# SOM_CD.net
KiCad netlist of a schematic drawn in Altium Designer
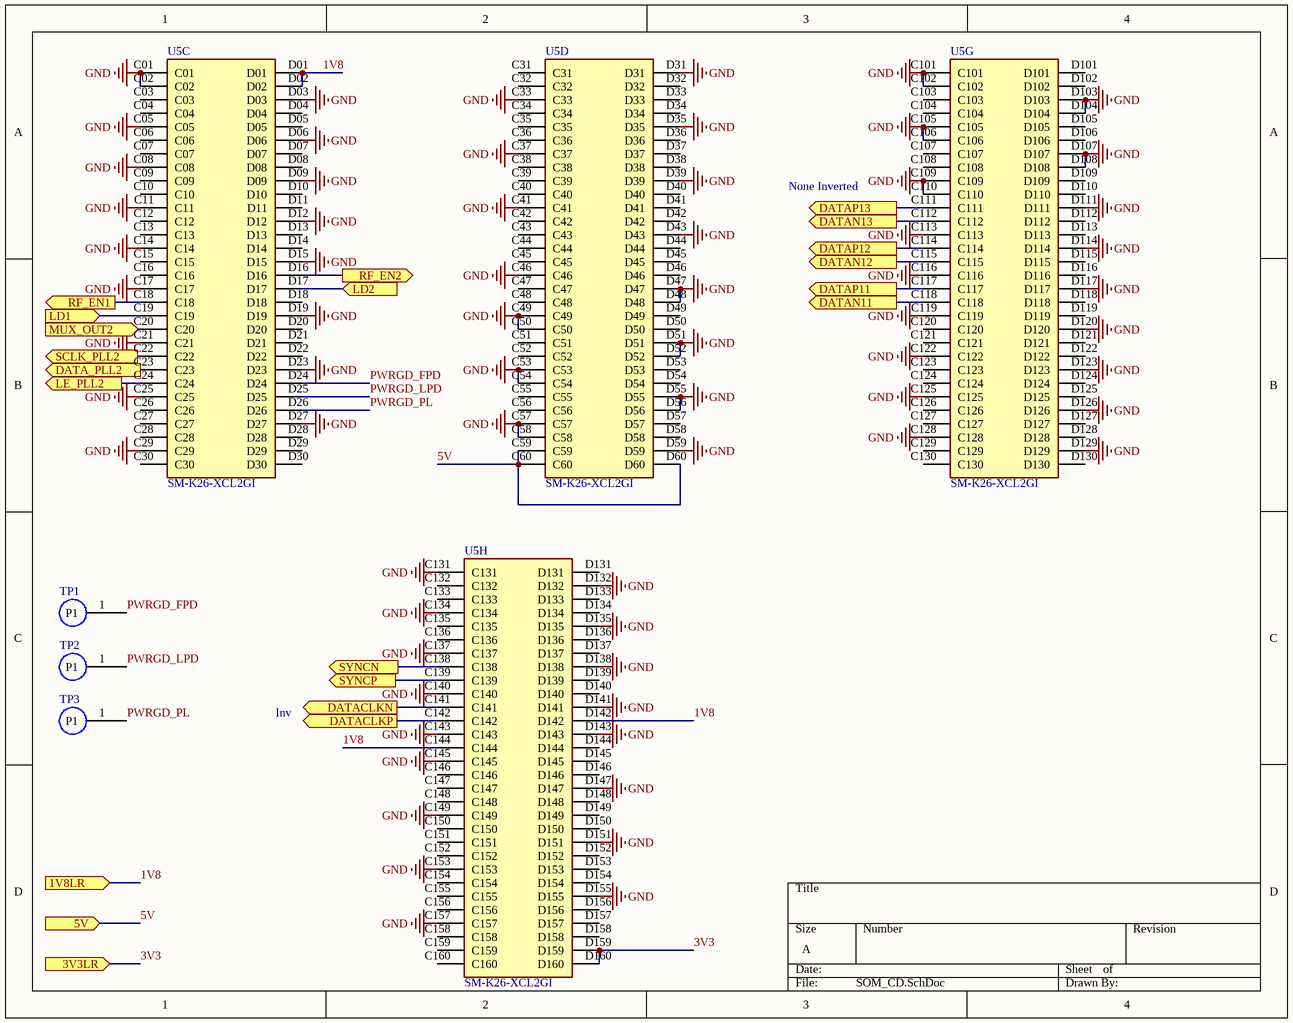
[diagram p0: SOM_CD.SchDoc]

(export (version "E")
  (design (tool "Eeschema 10.0.6"))
  (components
    (comp (ref "TP1") (value "~") (footprint "Testpoint") (libsource (lib "Schlib1") (part "Testpoint")))
    (comp (ref "TP2") (value "~") (footprint "Testpoint") (libsource (lib "Schlib1") (part "Testpoint")))
    (comp (ref "TP3") (value "~") (footprint "Testpoint") (libsource (lib "Schlib1") (part "Testpoint")))
    (comp (ref "U5")
      (value "SM-K26-XCL2GI")
      (footprint "MODULE_SM-K26-XCL2GI")
      (fields (field (name "MF") "Xilinx Inc."))
      (libsource (lib "Schlib1") (part "SM-K26-XCL2GI"))
    )
  )
  (nets
    (net (code "1") (name "/1V8") (class "Default")
      (node (ref "U5") (pin "C144") (pinfunction "C144_C144") (pintype "passive"))
      (node (ref "U5") (pin "D01") (pinfunction "D01_D01") (pintype "passive"))
      (node (ref "U5") (pin "D02") (pinfunction "D02_D02") (pintype "passive"))
      (node (ref "U5") (pin "D142") (pinfunction "D142_D142") (pintype "passive"))
    )
    (net (code "2") (name "/3V3") (class "Default")
      (node (ref "U5") (pin "D159") (pinfunction "D159_D159") (pintype "passive"))
      (node (ref "U5") (pin "D160") (pinfunction "D160_D160") (pintype "passive"))
    )
    (net (code "3") (name "/5V") (class "Default")
      (node (ref "U5") (pin "C59") (pinfunction "C59_C59") (pintype "passive"))
      (node (ref "U5") (pin "C60") (pinfunction "C60_C60") (pintype "passive"))
      (node (ref "U5") (pin "D60") (pinfunction "D60_D60") (pintype "passive"))
    )
    (net (code "4") (name "/DATACLKN") (class "Default")
      (node (ref "U5") (pin "C141") (pinfunction "C141_C141") (pintype "passive"))
    )
    (net (code "5") (name "/DATACLKP") (class "Default")
      (node (ref "U5") (pin "C142") (pinfunction "C142_C142") (pintype "passive"))
    )
    (net (code "6") (name "/DATAN11") (class "Default")
      (node (ref "U5") (pin "C118") (pinfunction "C118_C118") (pintype "passive"))
    )
    (net (code "7") (name "/DATAN12") (class "Default")
      (node (ref "U5") (pin "C115") (pinfunction "C115_C115") (pintype "passive"))
    )
    (net (code "8") (name "/DATAN13") (class "Default")
      (node (ref "U5") (pin "C112") (pinfunction "C112_C112") (pintype "passive"))
    )
    (net (code "9") (name "/DATAP11") (class "Default")
      (node (ref "U5") (pin "C117") (pinfunction "C117_C117") (pintype "passive"))
    )
    (net (code "10") (name "/DATAP12") (class "Default")
      (node (ref "U5") (pin "C114") (pinfunction "C114_C114") (pintype "passive"))
    )
    (net (code "11") (name "/DATAP13") (class "Default")
      (node (ref "U5") (pin "C111") (pinfunction "C111_C111") (pintype "passive"))
    )
    (net (code "12") (name "/DATA_PLL2") (class "Default")
      (node (ref "U5") (pin "C23") (pinfunction "C23_C23") (pintype "passive"))
    )
    (net (code "13") (name "/LD1") (class "Default")
      (node (ref "U5") (pin "C19") (pinfunction "C19_C19") (pintype "passive"))
    )
    (net (code "14") (name "/LD2") (class "Default")
      (node (ref "U5") (pin "D17") (pinfunction "D17_D17") (pintype "passive"))
    )
    (net (code "15") (name "/LE_PLL2") (class "Default")
      (node (ref "U5") (pin "C24") (pinfunction "C24_C24") (pintype "passive"))
    )
    (net (code "16") (name "/MUX_OUT2") (class "Default")
      (node (ref "U5") (pin "C20") (pinfunction "C20_C20") (pintype "passive"))
    )
    (net (code "17") (name "/PWRGD_FPD") (class "Default")
      (node (ref "TP1") (pin "1") (pinfunction "P1_1") (pintype "passive"))
      (node (ref "U5") (pin "D24") (pinfunction "D24_D24") (pintype "passive"))
    )
    (net (code "18") (name "/PWRGD_LPD") (class "Default")
      (node (ref "TP2") (pin "1") (pinfunction "P1_1") (pintype "passive"))
      (node (ref "U5") (pin "D25") (pinfunction "D25_D25") (pintype "passive"))
    )
    (net (code "19") (name "/PWRGD_PL") (class "Default")
      (node (ref "TP3") (pin "1") (pinfunction "P1_1") (pintype "passive"))
      (node (ref "U5") (pin "D26") (pinfunction "D26_D26") (pintype "passive"))
    )
    (net (code "20") (name "/RF_EN1") (class "Default")
      (node (ref "U5") (pin "C18") (pinfunction "C18_C18") (pintype "passive"))
    )
    (net (code "21") (name "/RF_EN2") (class "Default")
      (node (ref "U5") (pin "D16") (pinfunction "D16_D16") (pintype "passive"))
    )
    (net (code "22") (name "/SCLK_PLL2") (class "Default")
      (node (ref "U5") (pin "C22") (pinfunction "C22_C22") (pintype "passive"))
    )
    (net (code "23") (name "/SYNCN") (class "Default")
      (node (ref "U5") (pin "C138") (pinfunction "C138_C138") (pintype "passive"))
    )
    (net (code "24") (name "/SYNCP") (class "Default")
      (node (ref "U5") (pin "C139") (pinfunction "C139_C139") (pintype "passive"))
    )
    (net (code "25") (name "GND") (class "Default")
      (node (ref "U5") (pin "C01") (pinfunction "C01_C01") (pintype "passive"))
      (node (ref "U5") (pin "C02") (pinfunction "C02_C02") (pintype "passive"))
      (node (ref "U5") (pin "C05") (pinfunction "C05_C05") (pintype "passive"))
      (node (ref "U5") (pin "C08") (pinfunction "C08_C08") (pintype "passive"))
      (node (ref "U5") (pin "C101") (pinfunction "C101_C101") (pintype "passive"))
      (node (ref "U5") (pin "C102") (pinfunction "C102_C102") (pintype "passive"))
      (node (ref "U5") (pin "C105") (pinfunction "C105_C105") (pintype "passive"))
      (node (ref "U5") (pin "C106") (pinfunction "C106_C106") (pintype "passive"))
      (node (ref "U5") (pin "C109") (pinfunction "C109_C109") (pintype "passive"))
      (node (ref "U5") (pin "C11") (pinfunction "C11_C11") (pintype "passive"))
      (node (ref "U5") (pin "C110") (pinfunction "C110_C110") (pintype "passive"))
      (node (ref "U5") (pin "C113") (pinfunction "C113_C113") (pintype "passive"))
      (node (ref "U5") (pin "C116") (pinfunction "C116_C116") (pintype "passive"))
      (node (ref "U5") (pin "C119") (pinfunction "C119_C119") (pintype "passive"))
      (node (ref "U5") (pin "C122") (pinfunction "C122_C122") (pintype "passive"))
      (node (ref "U5") (pin "C125") (pinfunction "C125_C125") (pintype "passive"))
      (node (ref "U5") (pin "C128") (pinfunction "C128_C128") (pintype "passive"))
      (node (ref "U5") (pin "C131") (pinfunction "C131_C131") (pintype "passive"))
      (node (ref "U5") (pin "C134") (pinfunction "C134_C134") (pintype "passive"))
      (node (ref "U5") (pin "C137") (pinfunction "C137_C137") (pintype "passive"))
      (node (ref "U5") (pin "C14") (pinfunction "C14_C14") (pintype "passive"))
      (node (ref "U5") (pin "C140") (pinfunction "C140_C140") (pintype "passive"))
      (node (ref "U5") (pin "C143") (pinfunction "C143_C143") (pintype "passive"))
      (node (ref "U5") (pin "C145") (pinfunction "C145_C145") (pintype "passive"))
      (node (ref "U5") (pin "C149") (pinfunction "C149_C149") (pintype "passive"))
      (node (ref "U5") (pin "C153") (pinfunction "C153_C153") (pintype "passive"))
      (node (ref "U5") (pin "C157") (pinfunction "C157_C157") (pintype "passive"))
      (node (ref "U5") (pin "C17") (pinfunction "C17_C17") (pintype "passive"))
      (node (ref "U5") (pin "C21") (pinfunction "C21_C21") (pintype "passive"))
      (node (ref "U5") (pin "C25") (pinfunction "C25_C25") (pintype "passive"))
      (node (ref "U5") (pin "C29") (pinfunction "C29_C29") (pintype "passive"))
      (node (ref "U5") (pin "C33") (pinfunction "C33_C33") (pintype "passive"))
      (node (ref "U5") (pin "C37") (pinfunction "C37_C37") (pintype "passive"))
      (node (ref "U5") (pin "C41") (pinfunction "C41_C41") (pintype "passive"))
      (node (ref "U5") (pin "C46") (pinfunction "C46_C46") (pintype "passive"))
      (node (ref "U5") (pin "C49") (pinfunction "C49_C49") (pintype "passive"))
      (node (ref "U5") (pin "C50") (pinfunction "C50_C50") (pintype "passive"))
      (node (ref "U5") (pin "C53") (pinfunction "C53_C53") (pintype "passive"))
      (node (ref "U5") (pin "C54") (pinfunction "C54_C54") (pintype "passive"))
      (node (ref "U5") (pin "C57") (pinfunction "C57_C57") (pintype "passive"))
      (node (ref "U5") (pin "C58") (pinfunction "C58_C58") (pintype "passive"))
      (node (ref "U5") (pin "D03") (pinfunction "D03_D03") (pintype "passive"))
      (node (ref "U5") (pin "D06") (pinfunction "D06_D06") (pintype "passive"))
      (node (ref "U5") (pin "D09") (pinfunction "D09_D09") (pintype "passive"))
      (node (ref "U5") (pin "D103") (pinfunction "D103_D103") (pintype "passive"))
      (node (ref "U5") (pin "D104") (pinfunction "D104_D104") (pintype "passive"))
      (node (ref "U5") (pin "D107") (pinfunction "D107_D107") (pintype "passive"))
      (node (ref "U5") (pin "D108") (pinfunction "D108_D108") (pintype "passive"))
      (node (ref "U5") (pin "D111") (pinfunction "D111_D111") (pintype "passive"))
      (node (ref "U5") (pin "D114") (pinfunction "D114_D114") (pintype "passive"))
      (node (ref "U5") (pin "D117") (pinfunction "D117_D117") (pintype "passive"))
      (node (ref "U5") (pin "D12") (pinfunction "D12_D12") (pintype "passive"))
      (node (ref "U5") (pin "D120") (pinfunction "D120_D120") (pintype "passive"))
      (node (ref "U5") (pin "D123") (pinfunction "D123_D123") (pintype "passive"))
      (node (ref "U5") (pin "D126") (pinfunction "D126_D126") (pintype "passive"))
      (node (ref "U5") (pin "D129") (pinfunction "D129_D129") (pintype "passive"))
      (node (ref "U5") (pin "D132") (pinfunction "D132_D132") (pintype "passive"))
      (node (ref "U5") (pin "D135") (pinfunction "D135_D135") (pintype "passive"))
      (node (ref "U5") (pin "D138") (pinfunction "D138_D138") (pintype "passive"))
      (node (ref "U5") (pin "D141") (pinfunction "D141_D141") (pintype "passive"))
      (node (ref "U5") (pin "D143") (pinfunction "D143_D143") (pintype "passive"))
      (node (ref "U5") (pin "D147") (pinfunction "D147_D147") (pintype "passive"))
      (node (ref "U5") (pin "D15") (pinfunction "D15_D15") (pintype "passive"))
      (node (ref "U5") (pin "D151") (pinfunction "D151_D151") (pintype "passive"))
      (node (ref "U5") (pin "D155") (pinfunction "D155_D155") (pintype "passive"))
      (node (ref "U5") (pin "D19") (pinfunction "D19_D19") (pintype "passive"))
      (node (ref "U5") (pin "D23") (pinfunction "D23_D23") (pintype "passive"))
      (node (ref "U5") (pin "D27") (pinfunction "D27_D27") (pintype "passive"))
      (node (ref "U5") (pin "D31") (pinfunction "D31_D31") (pintype "passive"))
      (node (ref "U5") (pin "D35") (pinfunction "D35_D35") (pintype "passive"))
      (node (ref "U5") (pin "D39") (pinfunction "D39_D39") (pintype "passive"))
      (node (ref "U5") (pin "D43") (pinfunction "D43_D43") (pintype "passive"))
      (node (ref "U5") (pin "D47") (pinfunction "D47_D47") (pintype "passive"))
      (node (ref "U5") (pin "D48") (pinfunction "D48_D48") (pintype "passive"))
      (node (ref "U5") (pin "D51") (pinfunction "D51_D51") (pintype "passive"))
      (node (ref "U5") (pin "D52") (pinfunction "D52_D52") (pintype "passive"))
      (node (ref "U5") (pin "D55") (pinfunction "D55_D55") (pintype "passive"))
      (node (ref "U5") (pin "D56") (pinfunction "D56_D56") (pintype "passive"))
      (node (ref "U5") (pin "D59") (pinfunction "D59_D59") (pintype "passive"))
    )
    (net (code "26") (name "unconnected-(U5-PadC03)") (class "Default")
      (node (ref "U5") (pin "C03") (pinfunction "C03_C03") (pintype "passive"))
    )
    (net (code "27") (name "unconnected-(U5-PadC04)") (class "Default")
      (node (ref "U5") (pin "C04") (pinfunction "C04_C04") (pintype "passive"))
    )
    (net (code "28") (name "unconnected-(U5-PadC06)") (class "Default")
      (node (ref "U5") (pin "C06") (pinfunction "C06_C06") (pintype "passive"))
    )
    (net (code "29") (name "unconnected-(U5-PadC07)") (class "Default")
      (node (ref "U5") (pin "C07") (pinfunction "C07_C07") (pintype "passive"))
    )
    (net (code "30") (name "unconnected-(U5-PadC09)") (class "Default")
      (node (ref "U5") (pin "C09") (pinfunction "C09_C09") (pintype "passive"))
    )
    (net (code "31") (name "unconnected-(U5-PadC10)") (class "Default")
      (node (ref "U5") (pin "C10") (pinfunction "C10_C10") (pintype "passive"))
    )
    (net (code "32") (name "unconnected-(U5-PadC12)") (class "Default")
      (node (ref "U5") (pin "C12") (pinfunction "C12_C12") (pintype "passive"))
    )
    (net (code "33") (name "unconnected-(U5-PadC13)") (class "Default")
      (node (ref "U5") (pin "C13") (pinfunction "C13_C13") (pintype "passive"))
    )
    (net (code "34") (name "unconnected-(U5-PadC15)") (class "Default")
      (node (ref "U5") (pin "C15") (pinfunction "C15_C15") (pintype "passive"))
    )
    (net (code "35") (name "unconnected-(U5-PadC16)") (class "Default")
      (node (ref "U5") (pin "C16") (pinfunction "C16_C16") (pintype "passive"))
    )
    (net (code "36") (name "unconnected-(U5-PadC26)") (class "Default")
      (node (ref "U5") (pin "C26") (pinfunction "C26_C26") (pintype "passive"))
    )
    (net (code "37") (name "unconnected-(U5-PadC27)") (class "Default")
      (node (ref "U5") (pin "C27") (pinfunction "C27_C27") (pintype "passive"))
    )
    (net (code "38") (name "unconnected-(U5-PadC28)") (class "Default")
      (node (ref "U5") (pin "C28") (pinfunction "C28_C28") (pintype "passive"))
    )
    (net (code "39") (name "unconnected-(U5-PadC30)") (class "Default")
      (node (ref "U5") (pin "C30") (pinfunction "C30_C30") (pintype "passive"))
    )
    (net (code "40") (name "unconnected-(U5-PadC31)") (class "Default")
      (node (ref "U5") (pin "C31") (pinfunction "C31_C31") (pintype "passive"))
    )
    (net (code "41") (name "unconnected-(U5-PadC32)") (class "Default")
      (node (ref "U5") (pin "C32") (pinfunction "C32_C32") (pintype "passive"))
    )
    (net (code "42") (name "unconnected-(U5-PadC34)") (class "Default")
      (node (ref "U5") (pin "C34") (pinfunction "C34_C34") (pintype "passive"))
    )
    (net (code "43") (name "unconnected-(U5-PadC35)") (class "Default")
      (node (ref "U5") (pin "C35") (pinfunction "C35_C35") (pintype "passive"))
    )
    (net (code "44") (name "unconnected-(U5-PadC36)") (class "Default")
      (node (ref "U5") (pin "C36") (pinfunction "C36_C36") (pintype "passive"))
    )
    (net (code "45") (name "unconnected-(U5-PadC38)") (class "Default")
      (node (ref "U5") (pin "C38") (pinfunction "C38_C38") (pintype "passive"))
    )
    (net (code "46") (name "unconnected-(U5-PadC39)") (class "Default")
      (node (ref "U5") (pin "C39") (pinfunction "C39_C39") (pintype "passive"))
    )
    (net (code "47") (name "unconnected-(U5-PadC40)") (class "Default")
      (node (ref "U5") (pin "C40") (pinfunction "C40_C40") (pintype "passive"))
    )
    (net (code "48") (name "unconnected-(U5-PadC42)") (class "Default")
      (node (ref "U5") (pin "C42") (pinfunction "C42_C42") (pintype "passive"))
    )
    (net (code "49") (name "unconnected-(U5-PadC43)") (class "Default")
      (node (ref "U5") (pin "C43") (pinfunction "C43_C43") (pintype "passive"))
    )
    (net (code "50") (name "unconnected-(U5-PadC44)") (class "Default")
      (node (ref "U5") (pin "C44") (pinfunction "C44_C44") (pintype "passive"))
    )
    (net (code "51") (name "unconnected-(U5-PadC45)") (class "Default")
      (node (ref "U5") (pin "C45") (pinfunction "C45_C45") (pintype "passive"))
    )
    (net (code "52") (name "unconnected-(U5-PadC47)") (class "Default")
      (node (ref "U5") (pin "C47") (pinfunction "C47_C47") (pintype "passive"))
    )
    (net (code "53") (name "unconnected-(U5-PadC48)") (class "Default")
      (node (ref "U5") (pin "C48") (pinfunction "C48_C48") (pintype "passive"))
    )
    (net (code "54") (name "unconnected-(U5-PadC51)") (class "Default")
      (node (ref "U5") (pin "C51") (pinfunction "C51_C51") (pintype "passive"))
    )
    (net (code "55") (name "unconnected-(U5-PadC52)") (class "Default")
      (node (ref "U5") (pin "C52") (pinfunction "C52_C52") (pintype "passive"))
    )
    (net (code "56") (name "unconnected-(U5-PadC55)") (class "Default")
      (node (ref "U5") (pin "C55") (pinfunction "C55_C55") (pintype "passive"))
    )
    (net (code "57") (name "unconnected-(U5-PadC56)") (class "Default")
      (node (ref "U5") (pin "C56") (pinfunction "C56_C56") (pintype "passive"))
    )
    (net (code "58") (name "unconnected-(U5-PadC103)") (class "Default")
      (node (ref "U5") (pin "C103") (pinfunction "C103_C103") (pintype "passive"))
    )
    (net (code "59") (name "unconnected-(U5-PadC104)") (class "Default")
      (node (ref "U5") (pin "C104") (pinfunction "C104_C104") (pintype "passive"))
    )
    (net (code "60") (name "unconnected-(U5-PadC107)") (class "Default")
      (node (ref "U5") (pin "C107") (pinfunction "C107_C107") (pintype "passive"))
    )
    (net (code "61") (name "unconnected-(U5-PadC108)") (class "Default")
      (node (ref "U5") (pin "C108") (pinfunction "C108_C108") (pintype "passive"))
    )
    (net (code "62") (name "unconnected-(U5-PadC120)") (class "Default")
      (node (ref "U5") (pin "C120") (pinfunction "C120_C120") (pintype "passive"))
    )
    (net (code "63") (name "unconnected-(U5-PadC121)") (class "Default")
      (node (ref "U5") (pin "C121") (pinfunction "C121_C121") (pintype "passive"))
    )
    (net (code "64") (name "unconnected-(U5-PadC123)") (class "Default")
      (node (ref "U5") (pin "C123") (pinfunction "C123_C123") (pintype "passive"))
    )
    (net (code "65") (name "unconnected-(U5-PadC124)") (class "Default")
      (node (ref "U5") (pin "C124") (pinfunction "C124_C124") (pintype "passive"))
    )
    (net (code "66") (name "unconnected-(U5-PadC126)") (class "Default")
      (node (ref "U5") (pin "C126") (pinfunction "C126_C126") (pintype "passive"))
    )
    (net (code "67") (name "unconnected-(U5-PadC127)") (class "Default")
      (node (ref "U5") (pin "C127") (pinfunction "C127_C127") (pintype "passive"))
    )
    (net (code "68") (name "unconnected-(U5-PadC129)") (class "Default")
      (node (ref "U5") (pin "C129") (pinfunction "C129_C129") (pintype "passive"))
    )
    (net (code "69") (name "unconnected-(U5-PadC130)") (class "Default")
      (node (ref "U5") (pin "C130") (pinfunction "C130_C130") (pintype "passive"))
    )
    (net (code "70") (name "unconnected-(U5-PadC132)") (class "Default")
      (node (ref "U5") (pin "C132") (pinfunction "C132_C132") (pintype "passive"))
    )
    (net (code "71") (name "unconnected-(U5-PadC133)") (class "Default")
      (node (ref "U5") (pin "C133") (pinfunction "C133_C133") (pintype "passive"))
    )
    (net (code "72") (name "unconnected-(U5-PadC135)") (class "Default")
      (node (ref "U5") (pin "C135") (pinfunction "C135_C135") (pintype "passive"))
    )
    (net (code "73") (name "unconnected-(U5-PadC136)") (class "Default")
      (node (ref "U5") (pin "C136") (pinfunction "C136_C136") (pintype "passive"))
    )
    (net (code "74") (name "unconnected-(U5-PadC146)") (class "Default")
      (node (ref "U5") (pin "C146") (pinfunction "C146_C146") (pintype "passive"))
    )
    (net (code "75") (name "unconnected-(U5-PadC147)") (class "Default")
      (node (ref "U5") (pin "C147") (pinfunction "C147_C147") (pintype "passive"))
    )
    (net (code "76") (name "unconnected-(U5-PadC148)") (class "Default")
      (node (ref "U5") (pin "C148") (pinfunction "C148_C148") (pintype "passive"))
    )
    (net (code "77") (name "unconnected-(U5-PadC150)") (class "Default")
      (node (ref "U5") (pin "C150") (pinfunction "C150_C150") (pintype "passive"))
    )
    (net (code "78") (name "unconnected-(U5-PadC151)") (class "Default")
      (node (ref "U5") (pin "C151") (pinfunction "C151_C151") (pintype "passive"))
    )
    (net (code "79") (name "unconnected-(U5-PadC152)") (class "Default")
      (node (ref "U5") (pin "C152") (pinfunction "C152_C152") (pintype "passive"))
    )
    (net (code "80") (name "unconnected-(U5-PadC154)") (class "Default")
      (node (ref "U5") (pin "C154") (pinfunction "C154_C154") (pintype "passive"))
    )
    (net (code "81") (name "unconnected-(U5-PadC155)") (class "Default")
      (node (ref "U5") (pin "C155") (pinfunction "C155_C155") (pintype "passive"))
    )
    (net (code "82") (name "unconnected-(U5-PadC156)") (class "Default")
      (node (ref "U5") (pin "C156") (pinfunction "C156_C156") (pintype "passive"))
    )
    (net (code "83") (name "unconnected-(U5-PadC158)") (class "Default")
      (node (ref "U5") (pin "C158") (pinfunction "C158_C158") (pintype "passive"))
    )
    (net (code "84") (name "unconnected-(U5-PadC159)") (class "Default")
      (node (ref "U5") (pin "C159") (pinfunction "C159_C159") (pintype "passive"))
    )
    (net (code "85") (name "unconnected-(U5-PadC160)") (class "Default")
      (node (ref "U5") (pin "C160") (pinfunction "C160_C160") (pintype "passive"))
    )
    (net (code "86") (name "unconnected-(U5-PadD04)") (class "Default")
      (node (ref "U5") (pin "D04") (pinfunction "D04_D04") (pintype "passive"))
    )
    (net (code "87") (name "unconnected-(U5-PadD05)") (class "Default")
      (node (ref "U5") (pin "D05") (pinfunction "D05_D05") (pintype "passive"))
    )
    (net (code "88") (name "unconnected-(U5-PadD07)") (class "Default")
      (node (ref "U5") (pin "D07") (pinfunction "D07_D07") (pintype "passive"))
    )
    (net (code "89") (name "unconnected-(U5-PadD08)") (class "Default")
      (node (ref "U5") (pin "D08") (pinfunction "D08_D08") (pintype "passive"))
    )
    (net (code "90") (name "unconnected-(U5-PadD10)") (class "Default")
      (node (ref "U5") (pin "D10") (pinfunction "D10_D10") (pintype "passive"))
    )
    (net (code "91") (name "unconnected-(U5-PadD11)") (class "Default")
      (node (ref "U5") (pin "D11") (pinfunction "D11_D11") (pintype "passive"))
    )
    (net (code "92") (name "unconnected-(U5-PadD13)") (class "Default")
      (node (ref "U5") (pin "D13") (pinfunction "D13_D13") (pintype "passive"))
    )
    (net (code "93") (name "unconnected-(U5-PadD14)") (class "Default")
      (node (ref "U5") (pin "D14") (pinfunction "D14_D14") (pintype "passive"))
    )
    (net (code "94") (name "unconnected-(U5-PadD18)") (class "Default")
      (node (ref "U5") (pin "D18") (pinfunction "D18_D18") (pintype "passive"))
    )
    (net (code "95") (name "unconnected-(U5-PadD20)") (class "Default")
      (node (ref "U5") (pin "D20") (pinfunction "D20_D20") (pintype "passive"))
    )
    (net (code "96") (name "unconnected-(U5-PadD21)") (class "Default")
      (node (ref "U5") (pin "D21") (pinfunction "D21_D21") (pintype "passive"))
    )
    (net (code "97") (name "unconnected-(U5-PadD22)") (class "Default")
      (node (ref "U5") (pin "D22") (pinfunction "D22_D22") (pintype "passive"))
    )
    (net (code "98") (name "unconnected-(U5-PadD28)") (class "Default")
      (node (ref "U5") (pin "D28") (pinfunction "D28_D28") (pintype "passive"))
    )
    (net (code "99") (name "unconnected-(U5-PadD29)") (class "Default")
      (node (ref "U5") (pin "D29") (pinfunction "D29_D29") (pintype "passive"))
    )
    (net (code "100") (name "unconnected-(U5-PadD30)") (class "Default")
      (node (ref "U5") (pin "D30") (pinfunction "D30_D30") (pintype "passive"))
    )
    (net (code "101") (name "unconnected-(U5-PadD32)") (class "Default")
      (node (ref "U5") (pin "D32") (pinfunction "D32_D32") (pintype "passive"))
    )
    (net (code "102") (name "unconnected-(U5-PadD33)") (class "Default")
      (node (ref "U5") (pin "D33") (pinfunction "D33_D33") (pintype "passive"))
    )
    (net (code "103") (name "unconnected-(U5-PadD34)") (class "Default")
      (node (ref "U5") (pin "D34") (pinfunction "D34_D34") (pintype "passive"))
    )
    (net (code "104") (name "unconnected-(U5-PadD36)") (class "Default")
      (node (ref "U5") (pin "D36") (pinfunction "D36_D36") (pintype "passive"))
    )
    (net (code "105") (name "unconnected-(U5-PadD37)") (class "Default")
      (node (ref "U5") (pin "D37") (pinfunction "D37_D37") (pintype "passive"))
    )
    (net (code "106") (name "unconnected-(U5-PadD38)") (class "Default")
      (node (ref "U5") (pin "D38") (pinfunction "D38_D38") (pintype "passive"))
    )
    (net (code "107") (name "unconnected-(U5-PadD40)") (class "Default")
      (node (ref "U5") (pin "D40") (pinfunction "D40_D40") (pintype "passive"))
    )
    (net (code "108") (name "unconnected-(U5-PadD41)") (class "Default")
      (node (ref "U5") (pin "D41") (pinfunction "D41_D41") (pintype "passive"))
    )
    (net (code "109") (name "unconnected-(U5-PadD42)") (class "Default")
      (node (ref "U5") (pin "D42") (pinfunction "D42_D42") (pintype "passive"))
    )
    (net (code "110") (name "unconnected-(U5-PadD44)") (class "Default")
      (node (ref "U5") (pin "D44") (pinfunction "D44_D44") (pintype "passive"))
    )
    (net (code "111") (name "unconnected-(U5-PadD45)") (class "Default")
      (node (ref "U5") (pin "D45") (pinfunction "D45_D45") (pintype "passive"))
    )
    (net (code "112") (name "unconnected-(U5-PadD46)") (class "Default")
      (node (ref "U5") (pin "D46") (pinfunction "D46_D46") (pintype "passive"))
    )
    (net (code "113") (name "unconnected-(U5-PadD49)") (class "Default")
      (node (ref "U5") (pin "D49") (pinfunction "D49_D49") (pintype "passive"))
    )
    (net (code "114") (name "unconnected-(U5-PadD50)") (class "Default")
      (node (ref "U5") (pin "D50") (pinfunction "D50_D50") (pintype "passive"))
    )
    (net (code "115") (name "unconnected-(U5-PadD53)") (class "Default")
      (node (ref "U5") (pin "D53") (pinfunction "D53_D53") (pintype "passive"))
    )
    (net (code "116") (name "unconnected-(U5-PadD54)") (class "Default")
      (node (ref "U5") (pin "D54") (pinfunction "D54_D54") (pintype "passive"))
    )
    (net (code "117") (name "unconnected-(U5-PadD57)") (class "Default")
      (node (ref "U5") (pin "D57") (pinfunction "D57_D57") (pintype "passive"))
    )
    (net (code "118") (name "unconnected-(U5-PadD58)") (class "Default")
      (node (ref "U5") (pin "D58") (pinfunction "D58_D58") (pintype "passive"))
    )
    (net (code "119") (name "unconnected-(U5-PadD101)") (class "Default")
      (node (ref "U5") (pin "D101") (pinfunction "D101_D101") (pintype "passive"))
    )
    (net (code "120") (name "unconnected-(U5-PadD102)") (class "Default")
      (node (ref "U5") (pin "D102") (pinfunction "D102_D102") (pintype "passive"))
    )
    (net (code "121") (name "unconnected-(U5-PadD105)") (class "Default")
      (node (ref "U5") (pin "D105") (pinfunction "D105_D105") (pintype "passive"))
    )
    (net (code "122") (name "unconnected-(U5-PadD106)") (class "Default")
      (node (ref "U5") (pin "D106") (pinfunction "D106_D106") (pintype "passive"))
    )
    (net (code "123") (name "unconnected-(U5-PadD109)") (class "Default")
      (node (ref "U5") (pin "D109") (pinfunction "D109_D109") (pintype "passive"))
    )
    (net (code "124") (name "unconnected-(U5-PadD110)") (class "Default")
      (node (ref "U5") (pin "D110") (pinfunction "D110_D110") (pintype "passive"))
    )
    (net (code "125") (name "unconnected-(U5-PadD112)") (class "Default")
      (node (ref "U5") (pin "D112") (pinfunction "D112_D112") (pintype "passive"))
    )
    (net (code "126") (name "unconnected-(U5-PadD113)") (class "Default")
      (node (ref "U5") (pin "D113") (pinfunction "D113_D113") (pintype "passive"))
    )
    (net (code "127") (name "unconnected-(U5-PadD115)") (class "Default")
      (node (ref "U5") (pin "D115") (pinfunction "D115_D115") (pintype "passive"))
    )
    (net (code "128") (name "unconnected-(U5-PadD116)") (class "Default")
      (node (ref "U5") (pin "D116") (pinfunction "D116_D116") (pintype "passive"))
    )
    (net (code "129") (name "unconnected-(U5-PadD118)") (class "Default")
      (node (ref "U5") (pin "D118") (pinfunction "D118_D118") (pintype "passive"))
    )
    (net (code "130") (name "unconnected-(U5-PadD119)") (class "Default")
      (node (ref "U5") (pin "D119") (pinfunction "D119_D119") (pintype "passive"))
    )
    (net (code "131") (name "unconnected-(U5-PadD121)") (class "Default")
      (node (ref "U5") (pin "D121") (pinfunction "D121_D121") (pintype "passive"))
    )
    (net (code "132") (name "unconnected-(U5-PadD122)") (class "Default")
      (node (ref "U5") (pin "D122") (pinfunction "D122_D122") (pintype "passive"))
    )
    (net (code "133") (name "unconnected-(U5-PadD124)") (class "Default")
      (node (ref "U5") (pin "D124") (pinfunction "D124_D124") (pintype "passive"))
    )
    (net (code "134") (name "unconnected-(U5-PadD125)") (class "Default")
      (node (ref "U5") (pin "D125") (pinfunction "D125_D125") (pintype "passive"))
    )
    (net (code "135") (name "unconnected-(U5-PadD127)") (class "Default")
      (node (ref "U5") (pin "D127") (pinfunction "D127_D127") (pintype "passive"))
    )
    (net (code "136") (name "unconnected-(U5-PadD128)") (class "Default")
      (node (ref "U5") (pin "D128") (pinfunction "D128_D128") (pintype "passive"))
    )
    (net (code "137") (name "unconnected-(U5-PadD130)") (class "Default")
      (node (ref "U5") (pin "D130") (pinfunction "D130_D130") (pintype "passive"))
    )
    (net (code "138") (name "unconnected-(U5-PadD131)") (class "Default")
      (node (ref "U5") (pin "D131") (pinfunction "D131_D131") (pintype "passive"))
    )
    (net (code "139") (name "unconnected-(U5-PadD133)") (class "Default")
      (node (ref "U5") (pin "D133") (pinfunction "D133_D133") (pintype "passive"))
    )
    (net (code "140") (name "unconnected-(U5-PadD134)") (class "Default")
      (node (ref "U5") (pin "D134") (pinfunction "D134_D134") (pintype "passive"))
    )
    (net (code "141") (name "unconnected-(U5-PadD136)") (class "Default")
      (node (ref "U5") (pin "D136") (pinfunction "D136_D136") (pintype "passive"))
    )
    (net (code "142") (name "unconnected-(U5-PadD137)") (class "Default")
      (node (ref "U5") (pin "D137") (pinfunction "D137_D137") (pintype "passive"))
    )
    (net (code "143") (name "unconnected-(U5-PadD139)") (class "Default")
      (node (ref "U5") (pin "D139") (pinfunction "D139_D139") (pintype "passive"))
    )
    (net (code "144") (name "unconnected-(U5-PadD140)") (class "Default")
      (node (ref "U5") (pin "D140") (pinfunction "D140_D140") (pintype "passive"))
    )
    (net (code "145") (name "unconnected-(U5-PadD144)") (class "Default")
      (node (ref "U5") (pin "D144") (pinfunction "D144_D144") (pintype "passive"))
    )
    (net (code "146") (name "unconnected-(U5-PadD145)") (class "Default")
      (node (ref "U5") (pin "D145") (pinfunction "D145_D145") (pintype "passive"))
    )
    (net (code "147") (name "unconnected-(U5-PadD146)") (class "Default")
      (node (ref "U5") (pin "D146") (pinfunction "D146_D146") (pintype "passive"))
    )
    (net (code "148") (name "unconnected-(U5-PadD148)") (class "Default")
      (node (ref "U5") (pin "D148") (pinfunction "D148_D148") (pintype "passive"))
    )
    (net (code "149") (name "unconnected-(U5-PadD149)") (class "Default")
      (node (ref "U5") (pin "D149") (pinfunction "D149_D149") (pintype "passive"))
    )
    (net (code "150") (name "unconnected-(U5-PadD150)") (class "Default")
      (node (ref "U5") (pin "D150") (pinfunction "D150_D150") (pintype "passive"))
    )
    (net (code "151") (name "unconnected-(U5-PadD152)") (class "Default")
      (node (ref "U5") (pin "D152") (pinfunction "D152_D152") (pintype "passive"))
    )
    (net (code "152") (name "unconnected-(U5-PadD153)") (class "Default")
      (node (ref "U5") (pin "D153") (pinfunction "D153_D153") (pintype "passive"))
    )
    (net (code "153") (name "unconnected-(U5-PadD154)") (class "Default")
      (node (ref "U5") (pin "D154") (pinfunction "D154_D154") (pintype "passive"))
    )
    (net (code "154") (name "unconnected-(U5-PadD156)") (class "Default")
      (node (ref "U5") (pin "D156") (pinfunction "D156_D156") (pintype "passive"))
    )
    (net (code "155") (name "unconnected-(U5-PadD157)") (class "Default")
      (node (ref "U5") (pin "D157") (pinfunction "D157_D157") (pintype "passive"))
    )
    (net (code "156") (name "unconnected-(U5-PadD158)") (class "Default")
      (node (ref "U5") (pin "D158") (pinfunction "D158_D158") (pintype "passive"))
    )
  )
)
